# ssslidar_v1_0_blade_SIG_top.net
KiCad netlist of a schematic drawn in EAGLE
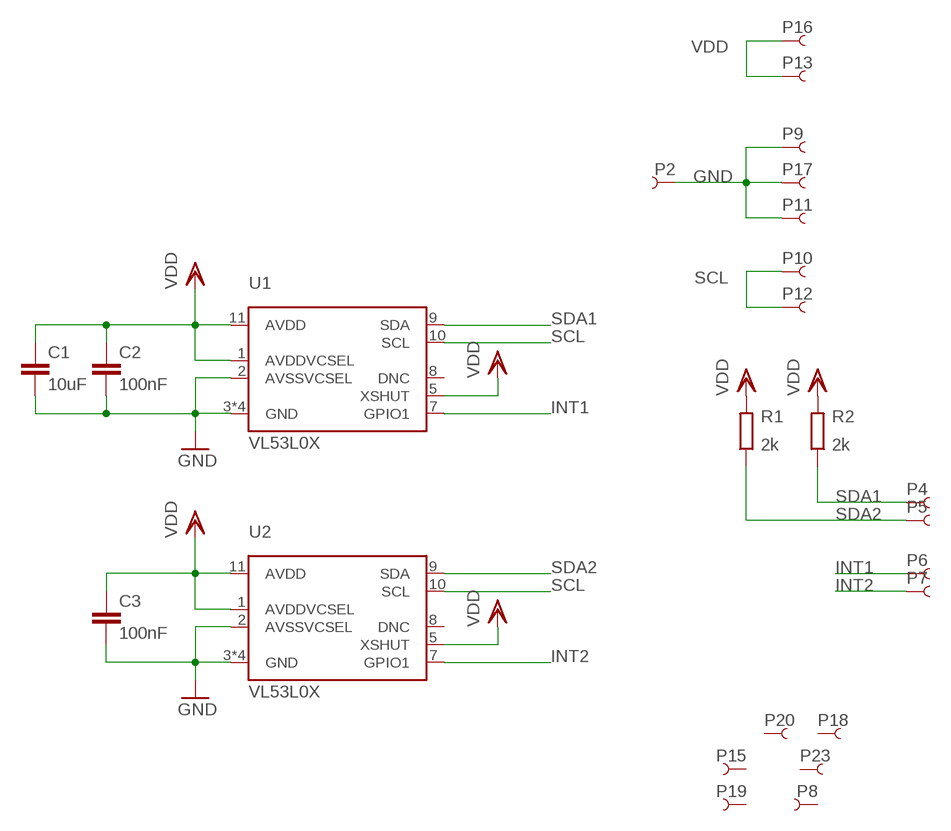
[diagram p0: schematic, sheet 1]

(export (version "E")
  (design (tool "Eeschema 10.0.6"))
  (components
    (comp (ref "C1")
      (value "10uF")
      (footprint "eagle-import:0805_N")
      (libsource (lib "eagle-import") (part "C0805"))
    )
    (comp (ref "C2")
      (value "100nF")
      (footprint "eagle-import:0402_N")
      (libsource (lib "eagle-import") (part "C0402"))
    )
    (comp (ref "C3")
      (value "100nF")
      (footprint "eagle-import:0402_N")
      (libsource (lib "eagle-import") (part "C0402"))
    )
    (comp (ref "P2")
      (value "PIN_SMD_1X1_RECT")
      (footprint "eagle-import:PIN_SMD_1X1_RECT")
      (libsource (lib "eagle-import") (part "PIN_SMD_1X1_RECT"))
    )
    (comp (ref "P4")
      (value "PIN_SMD_0.8X1_RECT")
      (footprint "eagle-import:PIN_SMD_0.8X1_RECT")
      (libsource (lib "eagle-import") (part "PIN_SMD_0.8X1_RECT"))
    )
    (comp (ref "P5")
      (value "PIN_SMD_0.8X1_RECT")
      (footprint "eagle-import:PIN_SMD_0.8X1_RECT")
      (libsource (lib "eagle-import") (part "PIN_SMD_0.8X1_RECT"))
    )
    (comp (ref "P6")
      (value "PIN_SMD_0.8X1_RECT")
      (footprint "eagle-import:PIN_SMD_0.8X1_RECT")
      (libsource (lib "eagle-import") (part "PIN_SMD_0.8X1_RECT"))
    )
    (comp (ref "P7")
      (value "PIN_SMD_0.8X1_RECT")
      (footprint "eagle-import:PIN_SMD_0.8X1_RECT")
      (libsource (lib "eagle-import") (part "PIN_SMD_0.8X1_RECT"))
    )
    (comp (ref "P8")
      (value "PIN_SMD_0.8X1_RECT")
      (footprint "eagle-import:PIN_SMD_0.8X1_RECT")
      (libsource (lib "eagle-import") (part "PIN_SMD_0.8X1_RECT"))
    )
    (comp (ref "P9")
      (value "PIN_SMD_1X1_RECT")
      (footprint "eagle-import:PIN_SMD_1X1_RECT")
      (libsource (lib "eagle-import") (part "PIN_SMD_1X1_RECT"))
    )
    (comp (ref "P10")
      (value "PIN_SMD_1X1_RECT")
      (footprint "eagle-import:PIN_SMD_1X1_RECT")
      (libsource (lib "eagle-import") (part "PIN_SMD_1X1_RECT"))
    )
    (comp (ref "P11")
      (value "PIN_SMD_1X2")
      (footprint "eagle-import:PIN_SMD_1X2")
      (libsource (lib "eagle-import") (part "PIN_SMD_1X2"))
    )
    (comp (ref "P12")
      (value "PIN_SMD_1X1_RECT")
      (footprint "eagle-import:PIN_SMD_1X1_RECT")
      (libsource (lib "eagle-import") (part "PIN_SMD_1X1_RECT"))
    )
    (comp (ref "P13")
      (value "PIN_SMD_1X1_RECT")
      (footprint "eagle-import:PIN_SMD_1X1_RECT")
      (libsource (lib "eagle-import") (part "PIN_SMD_1X1_RECT"))
    )
    (comp (ref "P15")
      (value "PIN_SMD_0.8X1_RECT")
      (footprint "eagle-import:PIN_SMD_0.8X1_RECT")
      (libsource (lib "eagle-import") (part "PIN_SMD_0.8X1_RECT"))
    )
    (comp (ref "P16")
      (value "PIN_SMD_1X1_RECT")
      (footprint "eagle-import:PIN_SMD_1X1_RECT")
      (libsource (lib "eagle-import") (part "PIN_SMD_1X1_RECT"))
    )
    (comp (ref "P17")
      (value "PIN_SMD_1X2")
      (footprint "eagle-import:PIN_SMD_1X2")
      (libsource (lib "eagle-import") (part "PIN_SMD_1X2"))
    )
    (comp (ref "P18")
      (value "PIN_SMD_0.8X1_RECT")
      (footprint "eagle-import:PIN_SMD_0.8X1_RECT")
      (libsource (lib "eagle-import") (part "PIN_SMD_0.8X1_RECT"))
    )
    (comp (ref "P19")
      (value "PIN_SMD_0.8X1_RECT")
      (footprint "eagle-import:PIN_SMD_0.8X1_RECT")
      (libsource (lib "eagle-import") (part "PIN_SMD_0.8X1_RECT"))
    )
    (comp (ref "P20")
      (value "PIN_SMD_0.8X1_RECT")
      (footprint "eagle-import:PIN_SMD_0.8X1_RECT")
      (libsource (lib "eagle-import") (part "PIN_SMD_0.8X1_RECT"))
    )
    (comp (ref "P23")
      (value "PIN_SMD_0.8X1_RECT")
      (footprint "eagle-import:PIN_SMD_0.8X1_RECT")
      (libsource (lib "eagle-import") (part "PIN_SMD_0.8X1_RECT"))
    )
    (comp (ref "R1")
      (value "2k")
      (footprint "eagle-import:0402_N")
      (libsource (lib "eagle-import") (part "R0402"))
    )
    (comp (ref "R2")
      (value "2k")
      (footprint "eagle-import:0402_N")
      (libsource (lib "eagle-import") (part "R0402"))
    )
    (comp (ref "U1")
      (value "VL53L0X")
      (footprint "eagle-import:VL53L0X")
      (libsource (lib "eagle-import") (part "VL53L0X"))
    )
    (comp (ref "U2")
      (value "VL53L0X")
      (footprint "eagle-import:VL53L0X")
      (libsource (lib "eagle-import") (part "VL53L0X"))
    )
  )
  (nets
    (net (code "1") (name "/INT1") (class "Default")
      (node (ref "P6") (pin "PIN") (pinfunction "1_PIN") (pintype "bidirectional"))
      (node (ref "U1") (pin "7") (pinfunction "GPIO1_7") (pintype "bidirectional"))
    )
    (net (code "2") (name "/INT2") (class "Default")
      (node (ref "P7") (pin "PIN") (pinfunction "1_PIN") (pintype "bidirectional"))
      (node (ref "U2") (pin "7") (pinfunction "GPIO1_7") (pintype "bidirectional"))
    )
    (net (code "3") (name "/SCL") (class "Default")
      (node (ref "P10") (pin "PIN") (pinfunction "1_PIN") (pintype "bidirectional"))
      (node (ref "P12") (pin "PIN") (pinfunction "1_PIN") (pintype "bidirectional"))
      (node (ref "U1") (pin "10") (pinfunction "SCL_10") (pintype "bidirectional"))
      (node (ref "U2") (pin "10") (pinfunction "SCL_10") (pintype "bidirectional"))
    )
    (net (code "4") (name "/SDA1") (class "Default")
      (node (ref "P4") (pin "PIN") (pinfunction "1_PIN") (pintype "bidirectional"))
      (node (ref "R2") (pin "1") (pinfunction "1_1") (pintype "passive"))
      (node (ref "U1") (pin "9") (pinfunction "SDA_9") (pintype "bidirectional"))
    )
    (net (code "5") (name "/SDA2") (class "Default")
      (node (ref "P5") (pin "PIN") (pinfunction "1_PIN") (pintype "bidirectional"))
      (node (ref "R1") (pin "1") (pinfunction "1_1") (pintype "passive"))
      (node (ref "U2") (pin "9") (pinfunction "SDA_9") (pintype "bidirectional"))
    )
    (net (code "6") (name "GND") (class "Default")
      (node (ref "C1") (pin "2") (pinfunction "2_2") (pintype "passive"))
      (node (ref "C2") (pin "2") (pinfunction "2_2") (pintype "passive"))
      (node (ref "C3") (pin "2") (pinfunction "2_2") (pintype "passive"))
      (node (ref "P11") (pin "P$1") (pinfunction "1_P$1") (pintype "bidirectional"))
      (node (ref "P17") (pin "P$1") (pinfunction "1_P$1") (pintype "bidirectional"))
      (node (ref "P2") (pin "PIN") (pinfunction "1_PIN") (pintype "bidirectional"))
      (node (ref "P9") (pin "PIN") (pinfunction "1_PIN") (pintype "bidirectional"))
      (node (ref "U1") (pin "12") (pinfunction "GND_12") (pintype "bidirectional"))
      (node (ref "U1") (pin "2") (pinfunction "AVSSVCSEL_2") (pintype "bidirectional"))
      (node (ref "U1") (pin "3") (pinfunction "GND_3") (pintype "bidirectional"))
      (node (ref "U1") (pin "4") (pinfunction "GND_4") (pintype "bidirectional"))
      (node (ref "U1") (pin "6") (pinfunction "GND_6") (pintype "bidirectional"))
      (node (ref "U2") (pin "12") (pinfunction "GND_12") (pintype "bidirectional"))
      (node (ref "U2") (pin "2") (pinfunction "AVSSVCSEL_2") (pintype "bidirectional"))
      (node (ref "U2") (pin "3") (pinfunction "GND_3") (pintype "bidirectional"))
      (node (ref "U2") (pin "4") (pinfunction "GND_4") (pintype "bidirectional"))
      (node (ref "U2") (pin "6") (pinfunction "GND_6") (pintype "bidirectional"))
    )
    (net (code "7") (name "VDD") (class "Default")
      (node (ref "C1") (pin "1") (pinfunction "1_1") (pintype "passive"))
      (node (ref "C2") (pin "1") (pinfunction "1_1") (pintype "passive"))
      (node (ref "C3") (pin "1") (pinfunction "1_1") (pintype "passive"))
      (node (ref "P13") (pin "PIN") (pinfunction "1_PIN") (pintype "bidirectional"))
      (node (ref "P16") (pin "PIN") (pinfunction "1_PIN") (pintype "bidirectional"))
      (node (ref "R1") (pin "2") (pinfunction "2_2") (pintype "passive"))
      (node (ref "R2") (pin "2") (pinfunction "2_2") (pintype "passive"))
      (node (ref "U1") (pin "1") (pinfunction "AVDDVCSEL_1") (pintype "bidirectional"))
      (node (ref "U1") (pin "11") (pinfunction "AVDD_11") (pintype "bidirectional"))
      (node (ref "U1") (pin "5") (pinfunction "XSHUT_5") (pintype "bidirectional"))
      (node (ref "U2") (pin "1") (pinfunction "AVDDVCSEL_1") (pintype "bidirectional"))
      (node (ref "U2") (pin "11") (pinfunction "AVDD_11") (pintype "bidirectional"))
      (node (ref "U2") (pin "5") (pinfunction "XSHUT_5") (pintype "bidirectional"))
    )
    (net (code "8") (name "unconnected-(P8-1-PadPIN)") (class "Default")
      (node (ref "P8") (pin "PIN") (pinfunction "1_PIN") (pintype "bidirectional"))
    )
    (net (code "9") (name "unconnected-(P15-1-PadPIN)") (class "Default")
      (node (ref "P15") (pin "PIN") (pinfunction "1_PIN") (pintype "bidirectional"))
    )
    (net (code "10") (name "unconnected-(P18-1-PadPIN)") (class "Default")
      (node (ref "P18") (pin "PIN") (pinfunction "1_PIN") (pintype "bidirectional"))
    )
    (net (code "11") (name "unconnected-(P19-1-PadPIN)") (class "Default")
      (node (ref "P19") (pin "PIN") (pinfunction "1_PIN") (pintype "bidirectional"))
    )
    (net (code "12") (name "unconnected-(P20-1-PadPIN)") (class "Default")
      (node (ref "P20") (pin "PIN") (pinfunction "1_PIN") (pintype "bidirectional"))
    )
    (net (code "13") (name "unconnected-(P23-1-PadPIN)") (class "Default")
      (node (ref "P23") (pin "PIN") (pinfunction "1_PIN") (pintype "bidirectional"))
    )
    (net (code "14") (name "unconnected-(U1-DNC-Pad8)") (class "Default")
      (node (ref "U1") (pin "8") (pinfunction "DNC_8") (pintype "bidirectional"))
    )
    (net (code "15") (name "unconnected-(U2-DNC-Pad8)") (class "Default")
      (node (ref "U2") (pin "8") (pinfunction "DNC_8") (pintype "bidirectional"))
    )
  )
)
